# gydrodrive_sensor.net
KiCad netlist of a schematic drawn in Altium Designer
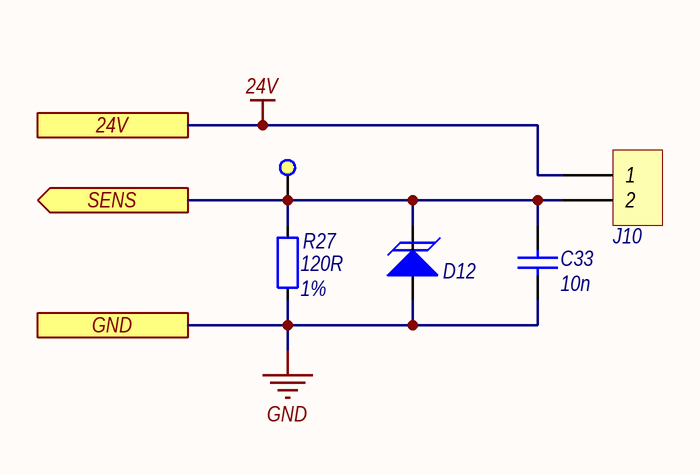
[diagram p0: gydrodrive_sensor.SchDoc]

(export (version "E")
  (design (tool "Eeschema 10.0.6"))
  (components
    (comp (ref "C33")
      (value "CAP_0805")
      (footprint "CAPC2012-0805M")
      (description "Конденсатор керамический, корпус 0805")
      (fields
        (field (name "CAPACITANCE") "10n")
        (field (name "PART NUMBER") "CAPC_0805")
        (field (name "VOLTAGE") "50V")
      )
      (libsource (lib "StdLib") (part "CAP"))
    )
    (comp (ref "D12")
      (value "SMBJ3V3-E3/52")
      (footprint "SMB_M")
      (description "Защитный диод (TVS)")
      (fields (field (name "VOLTAGE") "3V3"))
      (libsource (lib "StdLib") (part "TVS"))
    )
    (comp (ref "J10")
      (value "DG142V-5.08-02P")
      (footprint "DG142V-5.08-02P")
      (description "Клеммник 2-контактный, шаг 5.08 мм")
      (libsource (lib "StdLib") (part "PIN1x2"))
    )
    (comp (ref "R27")
      (value "RES_0805")
      (footprint "RESC2012-0805M")
      (description "Рез-р, корпус 0805")
      (fields
        (field (name "RESISTANCE") "120R")
        (field (name "PART NUMBER") "RESC_0805")
        (field (name "TOLERANCE") "1%")
      )
      (libsource (lib "StdLib") (part "RES"))
    )
    (comp (ref "TP9")
      (value "Test point 1")
      (footprint "TP_1")
      (description "Тестовый контакт круглый 1 мм")
      (libsource (lib "StdLib") (part "Test point"))
    )
  )
  (nets
    (net (code "1") (name "/SENS") (class "Default")
      (node (ref "C33") (pin "2") (pinfunction "2_2") (pintype "passive"))
      (node (ref "D12") (pin "1") (pinfunction "K_1") (pintype "passive"))
      (node (ref "J10") (pin "2") (pinfunction "2_2") (pintype "passive"))
      (node (ref "R27") (pin "2") (pinfunction "2_2") (pintype "passive"))
      (node (ref "TP9") (pin "1") (pinfunction "1_1") (pintype "passive"))
    )
    (net (code "2") (name "24V") (class "Default")
      (node (ref "J10") (pin "1") (pinfunction "1_1") (pintype "passive"))
    )
    (net (code "3") (name "GND") (class "Default")
      (node (ref "C33") (pin "1") (pinfunction "1_1") (pintype "passive"))
      (node (ref "D12") (pin "2") (pinfunction "A_2") (pintype "passive"))
      (node (ref "R27") (pin "1") (pinfunction "1_1") (pintype "passive"))
    )
  )
)
